# Power.net
KiCad netlist of a schematic drawn in Altium Designer
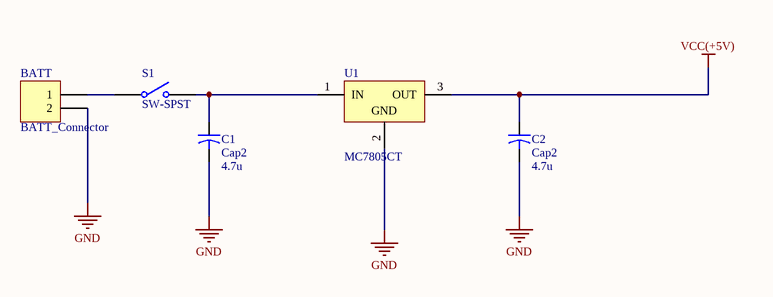
[diagram p0: Power.SchDoc]

(export (version "E")
  (design (tool "Eeschema 10.0.6"))
  (components
    (comp (ref "BATT")
      (value "BATT_Connector")
      (footprint "HDR1X2")
      (description "Header, 2-Pin")
      (fields (field (name "PUBLISHER") "Altium Limited"))
      (libsource (lib "Miscellaneous Connectors") (part "Header 2"))
    )
    (comp (ref "C1")
      (value "Cap2")
      (footprint "Capacitor 5mmx11mm")
      (description "Capacitor")
      (fields (field (name "ALTIUM_VALUE") "4.7u") (field (name "PUBLISHER") "Altium Limited"))
      (libsource (lib "Miscellaneous Devices") (part "Cap2"))
    )
    (comp (ref "C2")
      (value "Cap2")
      (footprint "Capacitor 5mmx11mm")
      (description "Capacitor")
      (fields (field (name "ALTIUM_VALUE") "4.7u") (field (name "PUBLISHER") "Altium Limited"))
      (libsource (lib "Miscellaneous Devices") (part "Cap2"))
    )
    (comp (ref "S1")
      (value "SW-SPST")
      (footprint "SPST-2")
      (description "Single-Pole, Single-Throw Switch")
      (fields (field (name "PUBLISHER") "Altium Limited"))
      (libsource (lib "Miscellaneous Devices") (part "SW-SPST"))
    )
    (comp (ref "U1")
      (value "MC7805CT")
      (footprint "221A-06")
      (description "Three-Terminal Positive Voltage Regulator")
      (fields (field (name "PUBLISHER") "Altium Limited"))
      (libsource (lib "ON Semi Power Mgt Voltage Regulator") (part "MC7805CT"))
    )
  )
  (nets
    (net (code "1") (name "GND") (class "Default")
      (node (ref "BATT") (pin "2") (pinfunction "2_2") (pintype "passive"))
      (node (ref "C1") (pin "2") (pinfunction "2_2") (pintype "passive"))
      (node (ref "C2") (pin "2") (pinfunction "2_2") (pintype "passive"))
      (node (ref "U1") (pin "2") (pinfunction "GND_2") (pintype "power_in"))
    )
    (net (code "2") (name "Net-(S1-COMMON)") (class "Default")
      (node (ref "BATT") (pin "1") (pinfunction "1_1") (pintype "passive"))
      (node (ref "S1") (pin "1") (pinfunction "COMMON_1") (pintype "passive"))
    )
    (net (code "3") (name "Net-(S1-NO)") (class "Default")
      (node (ref "C1") (pin "1") (pinfunction "1_1") (pintype "passive"))
      (node (ref "S1") (pin "2") (pinfunction "NO_2") (pintype "passive"))
      (node (ref "U1") (pin "1") (pinfunction "IN_1") (pintype "power_in"))
    )
    (net (code "4") (name "VCC(+5V)") (class "Default")
      (node (ref "C2") (pin "1") (pinfunction "1_1") (pintype "passive"))
      (node (ref "U1") (pin "3") (pinfunction "OUT_3") (pintype "power_in"))
    )
  )
)
